# mailboxNotifier.net
KiCad netlist of a schematic drawn in EAGLE
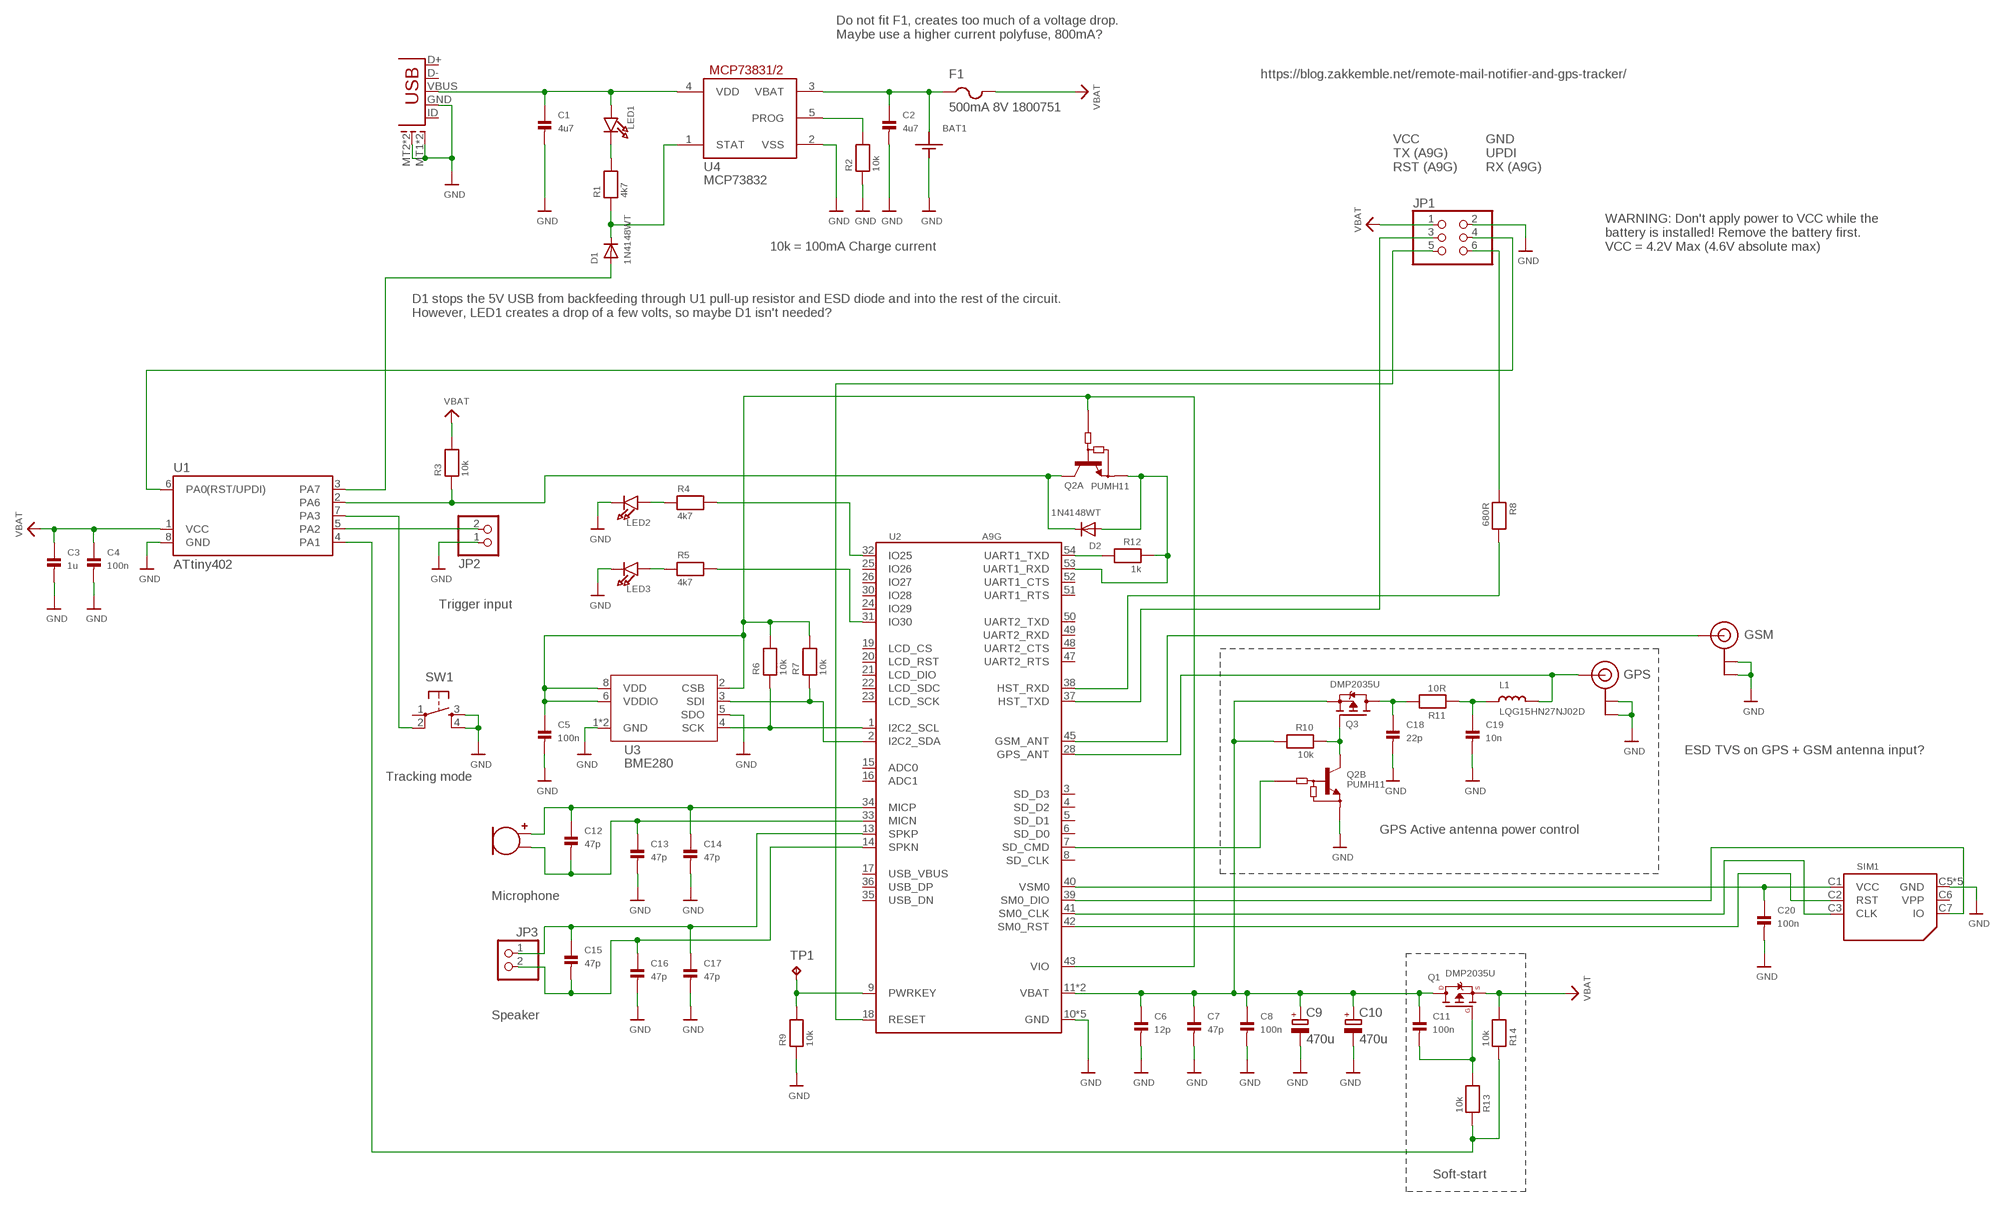
[diagram p0: schematic, sheet 1]

(export (version "E")
  (design (tool "Eeschema 10.0.6"))
  (components
    (comp (ref "BAT1")
      (value "BATTERY_HOLDER1XAAA_PCB")
      (footprint "eagle-import:BATT_HOLDER_AAA_PCB")
      (libsource (lib "eagle-import") (part "BATTERY_HOLDER1XAAA_PCB"))
    )
    (comp (ref "C1")
      (value "4u7")
      (footprint "eagle-import:0805_NO_OUTLINE")
      (libsource (lib "eagle-import") (part "zak_CAP_CERAMIC0805"))
    )
    (comp (ref "C2")
      (value "4u7")
      (footprint "eagle-import:0805_NO_OUTLINE")
      (libsource (lib "eagle-import") (part "zak_CAP_CERAMIC0805"))
    )
    (comp (ref "C3")
      (value "1u")
      (footprint "eagle-import:_0603MP")
      (libsource (lib "eagle-import") (part "CAP_CERAMIC_0603MP"))
    )
    (comp (ref "C4")
      (value "100n")
      (footprint "eagle-import:0402_SMALL")
      (libsource (lib "eagle-import") (part "CAP_CERAMIC0402_SMALL"))
    )
    (comp (ref "C5")
      (value "100n")
      (footprint "eagle-import:0402_SMALL")
      (libsource (lib "eagle-import") (part "CAP_CERAMIC0402_SMALL"))
    )
    (comp (ref "C6")
      (value "12p")
      (footprint "eagle-import:0402_SMALL")
      (libsource (lib "eagle-import") (part "CAP_CERAMIC0402_SMALL"))
    )
    (comp (ref "C7")
      (value "47p")
      (footprint "eagle-import:0402_SMALL")
      (libsource (lib "eagle-import") (part "CAP_CERAMIC0402_SMALL"))
    )
    (comp (ref "C8")
      (value "100n")
      (footprint "eagle-import:0402_SMALL")
      (libsource (lib "eagle-import") (part "CAP_CERAMIC0402_SMALL"))
    )
    (comp (ref "C9")
      (value "470u")
      (footprint "eagle-import:E2,5-6")
      (libsource (lib "eagle-import") (part "CPOL-EUE2.5-6"))
    )
    (comp (ref "C10")
      (value "470u")
      (footprint "eagle-import:E2,5-6")
      (libsource (lib "eagle-import") (part "CPOL-EUE2.5-6"))
    )
    (comp (ref "C11")
      (value "100n")
      (footprint "eagle-import:0402_SMALL")
      (libsource (lib "eagle-import") (part "CAP_CERAMIC0402_SMALL"))
    )
    (comp (ref "C12")
      (value "47p")
      (footprint "eagle-import:0402_SMALL")
      (libsource (lib "eagle-import") (part "CAP_CERAMIC0402_SMALL"))
    )
    (comp (ref "C13")
      (value "47p")
      (footprint "eagle-import:0402_SMALL")
      (libsource (lib "eagle-import") (part "CAP_CERAMIC0402_SMALL"))
    )
    (comp (ref "C14")
      (value "47p")
      (footprint "eagle-import:0402_SMALL")
      (libsource (lib "eagle-import") (part "CAP_CERAMIC0402_SMALL"))
    )
    (comp (ref "C15")
      (value "47p")
      (footprint "eagle-import:0402_SMALL")
      (libsource (lib "eagle-import") (part "CAP_CERAMIC0402_SMALL"))
    )
    (comp (ref "C16")
      (value "47p")
      (footprint "eagle-import:0402_SMALL")
      (libsource (lib "eagle-import") (part "CAP_CERAMIC0402_SMALL"))
    )
    (comp (ref "C17")
      (value "47p")
      (footprint "eagle-import:0402_SMALL")
      (libsource (lib "eagle-import") (part "CAP_CERAMIC0402_SMALL"))
    )
    (comp (ref "C18")
      (value "22p")
      (footprint "eagle-import:0402_SMALL")
      (libsource (lib "eagle-import") (part "CAP_CERAMIC0402_SMALL"))
    )
    (comp (ref "C19")
      (value "10n")
      (footprint "eagle-import:0402_SMALL")
      (libsource (lib "eagle-import") (part "CAP_CERAMIC0402_SMALL"))
    )
    (comp (ref "C20")
      (value "100n")
      (footprint "eagle-import:0402_SMALL")
      (libsource (lib "eagle-import") (part "CAP_CERAMIC0402_SMALL"))
    )
    (comp (ref "D1")
      (value "1N4148WT")
      (footprint "eagle-import:SOD-523")
      (libsource (lib "eagle-import") (part "DIODESOD-523"))
    )
    (comp (ref "D2")
      (value "1N4148WT")
      (footprint "eagle-import:SOD-523")
      (libsource (lib "eagle-import") (part "DIODESOD-523"))
    )
    (comp (ref "F1")
      (value "500mA 8V 1800751")
      (footprint "eagle-import:1206")
      (libsource (lib "eagle-import") (part "PTCFUSE1206"))
    )
    (comp (ref "JP1")
      (value "PINHD-2X3")
      (footprint "eagle-import:2X03")
      (libsource (lib "eagle-import") (part "PINHD-2X3"))
    )
    (comp (ref "JP2")
      (value "PINHD-1X2/90")
      (footprint "eagle-import:1X02_90")
      (libsource (lib "eagle-import") (part "PINHD-1X2/90"))
    )
    (comp (ref "JP3")
      (value "PINHD-1X2")
      (footprint "eagle-import:1X02")
      (libsource (lib "eagle-import") (part "PINHD-1X2"))
    )
    (comp (ref "L1")
      (value "LQG15HN27NJ02D")
      (footprint "eagle-import:0402_SMALL")
      (libsource (lib "eagle-import") (part "INDUCTOR0402_SMALL"))
    )
    (comp (ref "LED1")
      (value "LED0603_NOOUTLINE")
      (footprint "eagle-import:CHIPLED_0603_NOOUTLINE")
      (libsource (lib "eagle-import") (part "LED0603_NOOUTLINE"))
    )
    (comp (ref "LED2")
      (value "LED0603_NOOUTLINE")
      (footprint "eagle-import:CHIPLED_0603_NOOUTLINE")
      (libsource (lib "eagle-import") (part "LED0603_NOOUTLINE"))
    )
    (comp (ref "LED3")
      (value "LED0603_NOOUTLINE")
      (footprint "eagle-import:CHIPLED_0603_NOOUTLINE")
      (libsource (lib "eagle-import") (part "LED0603_NOOUTLINE"))
    )
    (comp (ref "MIC1")
      (value "MIC6MM_RA_SWAP")
      (footprint "eagle-import:MIC6MM_RA_SWAP")
      (libsource (lib "eagle-import") (part "MIC6MM_RA_SWAP"))
    )
    (comp (ref "Q1")
      (value "DMP2035U")
      (footprint "eagle-import:SOT-23-WIDE")
      (libsource (lib "eagle-import") (part "MOSFET-PSOT-23-WIDE"))
    )
    (comp (ref "Q2")
      (value "PUMH11")
      (footprint "eagle-import:SOT-363")
      (libsource (lib "eagle-import") (part "DUAL_NPNDIGITALSOT-363"))
    )
    (comp (ref "Q3")
      (value "DMP2035U")
      (footprint "eagle-import:SOT23-R")
      (libsource (lib "eagle-import") (part "MOSFET-P"))
    )
    (comp (ref "R1")
      (value "4k7")
      (footprint "eagle-import:0402_SMALL")
      (libsource (lib "eagle-import") (part "RESISTOR0402_SMALL"))
    )
    (comp (ref "R2")
      (value "10k")
      (footprint "eagle-import:0402_SMALL")
      (libsource (lib "eagle-import") (part "RESISTOR0402_SMALL"))
    )
    (comp (ref "R3")
      (value "10k")
      (footprint "eagle-import:0402_SMALL")
      (libsource (lib "eagle-import") (part "RESISTOR0402_SMALL"))
    )
    (comp (ref "R4")
      (value "4k7")
      (footprint "eagle-import:0402_SMALL")
      (libsource (lib "eagle-import") (part "RESISTOR0402_SMALL"))
    )
    (comp (ref "R5")
      (value "4k7")
      (footprint "eagle-import:0402_SMALL")
      (libsource (lib "eagle-import") (part "RESISTOR0402_SMALL"))
    )
    (comp (ref "R6")
      (value "10k")
      (footprint "eagle-import:0402_SMALL")
      (libsource (lib "eagle-import") (part "RESISTOR0402_SMALL"))
    )
    (comp (ref "R7")
      (value "10k")
      (footprint "eagle-import:0402_SMALL")
      (libsource (lib "eagle-import") (part "RESISTOR0402_SMALL"))
    )
    (comp (ref "R8")
      (value "680R")
      (footprint "eagle-import:0402_SMALL")
      (libsource (lib "eagle-import") (part "RESISTOR0402_SMALL"))
    )
    (comp (ref "R9")
      (value "10k")
      (footprint "eagle-import:0402_SMALL")
      (libsource (lib "eagle-import") (part "RESISTOR0402_SMALL"))
    )
    (comp (ref "R10")
      (value "10k")
      (footprint "eagle-import:0402_SMALL")
      (libsource (lib "eagle-import") (part "RESISTOR0402_SMALL"))
    )
    (comp (ref "R11")
      (value "10R")
      (footprint "eagle-import:0402_SMALL")
      (libsource (lib "eagle-import") (part "RESISTOR0402_SMALL"))
    )
    (comp (ref "R12")
      (value "1k")
      (footprint "eagle-import:0402_SMALL")
      (libsource (lib "eagle-import") (part "RESISTOR0402_SMALL"))
    )
    (comp (ref "R13")
      (value "10k")
      (footprint "eagle-import:0402_SMALL")
      (libsource (lib "eagle-import") (part "RESISTOR0402_SMALL"))
    )
    (comp (ref "R14")
      (value "10k")
      (footprint "eagle-import:0402_SMALL")
      (libsource (lib "eagle-import") (part "RESISTOR0402_SMALL"))
    )
    (comp (ref "SIM1")
      (value "SIMCARDSOCKET")
      (footprint "eagle-import:SIM_SOCKET1")
      (libsource (lib "eagle-import") (part "SIMCARDSOCKET"))
    )
    (comp (ref "SW1")
      (value "SPST_TACTG75_3X4")
      (footprint "eagle-import:TACT_SMD5")
      (libsource (lib "eagle-import") (part "SPST_TACTG75_3X4"))
    )
    (comp (ref "TP1")
      (value "TPTP10R")
      (footprint "eagle-import:TP10R")
      (libsource (lib "eagle-import") (part "TPTP10R"))
    )
    (comp (ref "U$38")
      (value "U.FL")
      (footprint "eagle-import:U.FL")
      (libsource (lib "eagle-import") (part "U.FL"))
    )
    (comp (ref "U$55")
      (value "U.FL")
      (footprint "eagle-import:U.FL")
      (libsource (lib "eagle-import") (part "U.FL"))
    )
    (comp (ref "U1")
      (value "ATtiny402")
      (footprint "eagle-import:SOIC8_150MIL_SMPAD")
      (libsource (lib "eagle-import") (part "ATTINY402SOIC8"))
    )
    (comp (ref "U2")
      (value "A9G")
      (footprint "eagle-import:A9G")
      (libsource (lib "eagle-import") (part "A9G"))
    )
    (comp (ref "U3")
      (value "BME280")
      (footprint "eagle-import:BME280")
      (libsource (lib "eagle-import") (part "BME280"))
    )
    (comp (ref "U4")
      (value "MCP73831/OT")
      (footprint "eagle-import:SOT23-5L")
      (libsource (lib "eagle-import") (part "MCP73831/OT"))
    )
    (comp (ref "USB1")
      (value "USB-MICROBSAFEBEE")
      (footprint "eagle-import:USB-MICROB_SAFEBEE")
      (libsource (lib "eagle-import") (part "USB-MICROBSAFEBEE"))
    )
  )
  (nets
    (net (code "1") (name "GND") (class "Default")
      (node (ref "BAT1") (pin "NEG") (pinfunction "NEG_NEG") (pintype "passive"))
      (node (ref "C1") (pin "2") (pinfunction "P$2_2") (pintype "passive"))
      (node (ref "C10") (pin "-") (pinfunction "-_-") (pintype "passive"))
      (node (ref "C13") (pin "2") (pinfunction "P$2_2") (pintype "passive"))
      (node (ref "C14") (pin "2") (pinfunction "P$2_2") (pintype "passive"))
      (node (ref "C16") (pin "2") (pinfunction "P$2_2") (pintype "passive"))
      (node (ref "C17") (pin "2") (pinfunction "P$2_2") (pintype "passive"))
      (node (ref "C18") (pin "2") (pinfunction "P$2_2") (pintype "passive"))
      (node (ref "C19") (pin "2") (pinfunction "P$2_2") (pintype "passive"))
      (node (ref "C2") (pin "2") (pinfunction "P$2_2") (pintype "passive"))
      (node (ref "C20") (pin "2") (pinfunction "P$2_2") (pintype "passive"))
      (node (ref "C3") (pin "2") (pinfunction "P$2_2") (pintype "passive"))
      (node (ref "C4") (pin "2") (pinfunction "P$2_2") (pintype "passive"))
      (node (ref "C5") (pin "2") (pinfunction "P$2_2") (pintype "passive"))
      (node (ref "C6") (pin "2") (pinfunction "P$2_2") (pintype "passive"))
      (node (ref "C7") (pin "2") (pinfunction "P$2_2") (pintype "passive"))
      (node (ref "C8") (pin "2") (pinfunction "P$2_2") (pintype "passive"))
      (node (ref "C9") (pin "-") (pinfunction "-_-") (pintype "passive"))
      (node (ref "JP1") (pin "2") (pinfunction "2_2") (pintype "passive"))
      (node (ref "JP2") (pin "1") (pinfunction "1_1") (pintype "passive"))
      (node (ref "LED2") (pin "C") (pinfunction "C_C") (pintype "passive"))
      (node (ref "LED3") (pin "C") (pinfunction "C_C") (pintype "passive"))
      (node (ref "Q2") (pin "4") (pinfunction "E_4") (pintype "passive"))
      (node (ref "R2") (pin "1") (pinfunction "1_1") (pintype "passive"))
      (node (ref "R9") (pin "1") (pinfunction "1_1") (pintype "passive"))
      (node (ref "SIM1") (pin "C5") (pinfunction "GND_C5") (pintype "bidirectional"))
      (node (ref "SIM1") (pin "GND1") (pinfunction "GND_GND1") (pintype "bidirectional"))
      (node (ref "SIM1") (pin "GND2") (pinfunction "GND_GND2") (pintype "bidirectional"))
      (node (ref "SIM1") (pin "GND3") (pinfunction "GND_GND3") (pintype "bidirectional"))
      (node (ref "SIM1") (pin "GND4") (pinfunction "GND_GND4") (pintype "bidirectional"))
      (node (ref "SW1") (pin "3") (pinfunction "S_3") (pintype "passive"))
      (node (ref "SW1") (pin "4") (pinfunction "S1_4") (pintype "passive"))
      (node (ref "U$38") (pin "1") (pinfunction "GND_1") (pintype "passive"))
      (node (ref "U$38") (pin "2") (pinfunction "GND_2") (pintype "passive"))
      (node (ref "U$55") (pin "1") (pinfunction "GND_1") (pintype "passive"))
      (node (ref "U$55") (pin "2") (pinfunction "GND_2") (pintype "passive"))
      (node (ref "U1") (pin "8") (pinfunction "GND_8") (pintype "power_in"))
      (node (ref "U2") (pin "10") (pinfunction "GND_10") (pintype "bidirectional"))
      (node (ref "U2") (pin "27") (pinfunction "GND_27") (pintype "bidirectional"))
      (node (ref "U2") (pin "29") (pinfunction "GND_29") (pintype "bidirectional"))
      (node (ref "U2") (pin "44") (pinfunction "GND_44") (pintype "bidirectional"))
      (node (ref "U2") (pin "46") (pinfunction "GND_46") (pintype "bidirectional"))
      (node (ref "U3") (pin "1") (pinfunction "GND_1") (pintype "bidirectional"))
      (node (ref "U3") (pin "5") (pinfunction "SDO_5") (pintype "bidirectional"))
      (node (ref "U3") (pin "7") (pinfunction "GND_7") (pintype "bidirectional"))
      (node (ref "U4") (pin "2") (pinfunction "VSS_2") (pintype "power_in"))
      (node (ref "USB1") (pin "GND") (pinfunction "GND_GND") (pintype "bidirectional"))
      (node (ref "USB1") (pin "MT1") (pinfunction "SHEILD1_MT1") (pintype "bidirectional"))
      (node (ref "USB1") (pin "MT2") (pinfunction "SHEILD2_MT2") (pintype "bidirectional"))
      (node (ref "USB1") (pin "MT3") (pinfunction "SHEILD1_MT3") (pintype "bidirectional"))
      (node (ref "USB1") (pin "MT4") (pinfunction "SHEILD2_MT4") (pintype "bidirectional"))
    )
    (net (code "2") (name "Net-(C1-P$1)") (class "Default")
      (node (ref "C1") (pin "1") (pinfunction "P$1_1") (pintype "passive"))
      (node (ref "LED1") (pin "A") (pinfunction "A_A") (pintype "passive"))
      (node (ref "U4") (pin "4") (pinfunction "VDD_4") (pintype "power_in"))
      (node (ref "USB1") (pin "VBUS") (pinfunction "VBUS_VBUS") (pintype "bidirectional"))
    )
    (net (code "3") (name "Net-(C2-P$1)") (class "Default")
      (node (ref "BAT1") (pin "POS") (pinfunction "POS_POS") (pintype "power_in"))
      (node (ref "C2") (pin "1") (pinfunction "P$1_1") (pintype "passive"))
      (node (ref "F1") (pin "1") (pinfunction "1_1") (pintype "passive"))
      (node (ref "U4") (pin "3") (pinfunction "VBAT_3") (pintype "bidirectional"))
    )
    (net (code "4") (name "Net-(C5-P$1)") (class "Default")
      (node (ref "C5") (pin "1") (pinfunction "P$1_1") (pintype "passive"))
      (node (ref "Q2") (pin "2") (pinfunction "B_2") (pintype "passive"))
      (node (ref "R6") (pin "2") (pinfunction "2_2") (pintype "passive"))
      (node (ref "R7") (pin "2") (pinfunction "2_2") (pintype "passive"))
      (node (ref "U2") (pin "43") (pinfunction "VIO_43") (pintype "bidirectional"))
      (node (ref "U3") (pin "2") (pinfunction "CSB_2") (pintype "bidirectional"))
      (node (ref "U3") (pin "6") (pinfunction "VDDIO_6") (pintype "bidirectional"))
      (node (ref "U3") (pin "8") (pinfunction "VDD_8") (pintype "bidirectional"))
    )
    (net (code "5") (name "Net-(C11-P$1)") (class "Default")
      (node (ref "C10") (pin "+") (pinfunction "+_+") (pintype "passive"))
      (node (ref "C11") (pin "1") (pinfunction "P$1_1") (pintype "passive"))
      (node (ref "C6") (pin "1") (pinfunction "P$1_1") (pintype "passive"))
      (node (ref "C7") (pin "1") (pinfunction "P$1_1") (pintype "passive"))
      (node (ref "C8") (pin "1") (pinfunction "P$1_1") (pintype "passive"))
      (node (ref "C9") (pin "+") (pinfunction "+_+") (pintype "passive"))
      (node (ref "Q1") (pin "3") (pinfunction "D_3") (pintype "passive"))
      (node (ref "Q3") (pin "2") (pinfunction "S_2") (pintype "passive"))
      (node (ref "R10") (pin "2") (pinfunction "2_2") (pintype "passive"))
      (node (ref "U2") (pin "11") (pinfunction "VBAT_11") (pintype "bidirectional"))
      (node (ref "U2") (pin "12") (pinfunction "VBAT_12") (pintype "bidirectional"))
    )
    (net (code "6") (name "Net-(C11-P$2)") (class "Default")
      (node (ref "C11") (pin "2") (pinfunction "P$2_2") (pintype "passive"))
      (node (ref "Q1") (pin "1") (pinfunction "G_1") (pintype "passive"))
      (node (ref "R13") (pin "2") (pinfunction "2_2") (pintype "passive"))
    )
    (net (code "7") (name "Net-(C12-P$1)") (class "Default")
      (node (ref "C12") (pin "1") (pinfunction "P$1_1") (pintype "passive"))
      (node (ref "C14") (pin "1") (pinfunction "P$1_1") (pintype "passive"))
      (node (ref "MIC1") (pin "POS") (pinfunction "POS_POS") (pintype "bidirectional"))
      (node (ref "U2") (pin "34") (pinfunction "MICP_34") (pintype "bidirectional"))
    )
    (net (code "8") (name "Net-(C12-P$2)") (class "Default")
      (node (ref "C12") (pin "2") (pinfunction "P$2_2") (pintype "passive"))
      (node (ref "C13") (pin "1") (pinfunction "P$1_1") (pintype "passive"))
      (node (ref "MIC1") (pin "NEG") (pinfunction "NEG_NEG") (pintype "bidirectional"))
      (node (ref "U2") (pin "33") (pinfunction "MICN_33") (pintype "bidirectional"))
    )
    (net (code "9") (name "Net-(C15-P$1)") (class "Default")
      (node (ref "C15") (pin "1") (pinfunction "P$1_1") (pintype "passive"))
      (node (ref "C17") (pin "1") (pinfunction "P$1_1") (pintype "passive"))
      (node (ref "JP3") (pin "1") (pinfunction "1_1") (pintype "passive"))
      (node (ref "U2") (pin "13") (pinfunction "SPKP_13") (pintype "bidirectional"))
    )
    (net (code "10") (name "Net-(C15-P$2)") (class "Default")
      (node (ref "C15") (pin "2") (pinfunction "P$2_2") (pintype "passive"))
      (node (ref "C16") (pin "1") (pinfunction "P$1_1") (pintype "passive"))
      (node (ref "JP3") (pin "2") (pinfunction "2_2") (pintype "passive"))
      (node (ref "U2") (pin "14") (pinfunction "SPKN_14") (pintype "bidirectional"))
    )
    (net (code "11") (name "Net-(C18-P$1)") (class "Default")
      (node (ref "C18") (pin "1") (pinfunction "P$1_1") (pintype "passive"))
      (node (ref "Q3") (pin "3") (pinfunction "D_3") (pintype "passive"))
      (node (ref "R11") (pin "2") (pinfunction "2_2") (pintype "passive"))
    )
    (net (code "12") (name "Net-(C19-P$1)") (class "Default")
      (node (ref "C19") (pin "1") (pinfunction "P$1_1") (pintype "passive"))
      (node (ref "L1") (pin "1") (pinfunction "1_1") (pintype "passive"))
      (node (ref "R11") (pin "1") (pinfunction "1_1") (pintype "passive"))
    )
    (net (code "13") (name "Net-(C20-P$1)") (class "Default")
      (node (ref "C20") (pin "1") (pinfunction "P$1_1") (pintype "passive"))
      (node (ref "SIM1") (pin "C1") (pinfunction "VCC_C1") (pintype "bidirectional"))
      (node (ref "U2") (pin "40") (pinfunction "VSM0_40") (pintype "bidirectional"))
    )
    (net (code "14") (name "Net-(D1-C)") (class "Default")
      (node (ref "D1") (pin "K") (pinfunction "C_K") (pintype "passive"))
      (node (ref "R1") (pin "1") (pinfunction "1_1") (pintype "passive"))
      (node (ref "U4") (pin "1") (pinfunction "STAT_1") (pintype "output"))
    )
    (net (code "15") (name "Net-(D2-C)") (class "Default")
      (node (ref "D2") (pin "K") (pinfunction "C_K") (pintype "passive"))
      (node (ref "Q2") (pin "6") (pinfunction "C_6") (pintype "passive"))
      (node (ref "R3") (pin "1") (pinfunction "1_1") (pintype "passive"))
      (node (ref "U1") (pin "2") (pinfunction "PA6_2") (pintype "bidirectional"))
    )
    (net (code "16") (name "Net-(JP1-Pad6)") (class "Default")
      (node (ref "JP1") (pin "6") (pinfunction "6_6") (pintype "passive"))
      (node (ref "R8") (pin "1") (pinfunction "1_1") (pintype "passive"))
    )
    (net (code "17") (name "Net-(LED1-PadC)") (class "Default")
      (node (ref "LED1") (pin "C") (pinfunction "C_C") (pintype "passive"))
      (node (ref "R1") (pin "2") (pinfunction "2_2") (pintype "passive"))
    )
    (net (code "18") (name "Net-(LED2-PadA)") (class "Default")
      (node (ref "LED2") (pin "A") (pinfunction "A_A") (pintype "passive"))
      (node (ref "R4") (pin "1") (pinfunction "1_1") (pintype "passive"))
    )
    (net (code "19") (name "Net-(LED3-PadA)") (class "Default")
      (node (ref "LED3") (pin "A") (pinfunction "A_A") (pintype "passive"))
      (node (ref "R5") (pin "1") (pinfunction "1_1") (pintype "passive"))
    )
    (net (code "20") (name "Net-(Q2A-E)") (class "Default")
      (node (ref "D2") (pin "A") (pinfunction "A_A") (pintype "passive"))
      (node (ref "Q2") (pin "1") (pinfunction "E_1") (pintype "passive"))
      (node (ref "R12") (pin "1") (pinfunction "1_1") (pintype "passive"))
      (node (ref "U2") (pin "53") (pinfunction "UART1_RXD_53") (pintype "bidirectional"))
    )
    (net (code "21") (name "Net-(Q2B-B)") (class "Default")
      (node (ref "Q2") (pin "5") (pinfunction "B_5") (pintype "passive"))
      (node (ref "U2") (pin "7") (pinfunction "SD_CMD_7") (pintype "bidirectional"))
    )
    (net (code "22") (name "Net-(Q2B-C)") (class "Default")
      (node (ref "Q2") (pin "3") (pinfunction "C_3") (pintype "passive"))
      (node (ref "Q3") (pin "1") (pinfunction "G_1") (pintype "passive"))
      (node (ref "R10") (pin "1") (pinfunction "1_1") (pintype "passive"))
    )
    (net (code "23") (name "Net-(SIM1-CLK)") (class "Default")
      (node (ref "SIM1") (pin "C3") (pinfunction "CLK_C3") (pintype "bidirectional"))
      (node (ref "U2") (pin "41") (pinfunction "SM0_CLK_41") (pintype "bidirectional"))
    )
    (net (code "24") (name "Net-(SIM1-IO)") (class "Default")
      (node (ref "SIM1") (pin "C7") (pinfunction "IO_C7") (pintype "bidirectional"))
      (node (ref "U2") (pin "39") (pinfunction "SM0_DIO_39") (pintype "bidirectional"))
    )
    (net (code "25") (name "Net-(SIM1-RST)") (class "Default")
      (node (ref "SIM1") (pin "C2") (pinfunction "RST_C2") (pintype "bidirectional"))
      (node (ref "U2") (pin "42") (pinfunction "SM0_RST_42") (pintype "bidirectional"))
    )
    (net (code "26") (name "Net-(SW1-P1)") (class "Default")
      (node (ref "SW1") (pin "2") (pinfunction "P1_2") (pintype "passive"))
      (node (ref "U1") (pin "7") (pinfunction "PA3_7") (pintype "bidirectional"))
    )
    (net (code "27") (name "Net-(U$38-SIGNAL)") (class "Default")
      (node (ref "L1") (pin "2") (pinfunction "2_2") (pintype "passive"))
      (node (ref "U$38") (pin "3") (pinfunction "SIGNAL_3") (pintype "passive"))
      (node (ref "U2") (pin "28") (pinfunction "GPS_ANT_28") (pintype "bidirectional"))
    )
    (net (code "28") (name "Net-(U$55-SIGNAL)") (class "Default")
      (node (ref "U$55") (pin "3") (pinfunction "SIGNAL_3") (pintype "passive"))
      (node (ref "U2") (pin "45") (pinfunction "GSM_ANT_45") (pintype "bidirectional"))
    )
    (net (code "29") (name "Net-(U1-PA0(RST{slash}UPDI))") (class "Default")
      (node (ref "JP1") (pin "4") (pinfunction "4_4") (pintype "passive"))
      (node (ref "U1") (pin "6") (pinfunction "PA0(RST/UPDI)_6") (pintype "input"))
    )
    (net (code "30") (name "Net-(U1-PA1)") (class "Default")
      (node (ref "R13") (pin "1") (pinfunction "1_1") (pintype "passive"))
      (node (ref "R14") (pin "1") (pinfunction "1_1") (pintype "passive"))
      (node (ref "U1") (pin "4") (pinfunction "PA1_4") (pintype "bidirectional"))
    )
    (net (code "31") (name "Net-(U1-PA2)") (class "Default")
      (node (ref "JP2") (pin "2") (pinfunction "2_2") (pintype "passive"))
      (node (ref "U1") (pin "5") (pinfunction "PA2_5") (pintype "bidirectional"))
    )
    (net (code "32") (name "Net-(U1-PA7)") (class "Default")
      (node (ref "D1") (pin "A") (pinfunction "A_A") (pintype "passive"))
      (node (ref "U1") (pin "3") (pinfunction "PA7_3") (pintype "bidirectional"))
    )
    (net (code "33") (name "Net-(U2-HST_RXD)") (class "Default")
      (node (ref "R8") (pin "2") (pinfunction "2_2") (pintype "passive"))
      (node (ref "U2") (pin "38") (pinfunction "HST_RXD_38") (pintype "bidirectional"))
    )
    (net (code "34") (name "Net-(U2-HST_TXD)") (class "Default")
      (node (ref "JP1") (pin "3") (pinfunction "3_3") (pintype "passive"))
      (node (ref "U2") (pin "37") (pinfunction "HST_TXD_37") (pintype "bidirectional"))
    )
    (net (code "35") (name "Net-(U2-I2C2_SCL)") (class "Default")
      (node (ref "R6") (pin "1") (pinfunction "1_1") (pintype "passive"))
      (node (ref "U2") (pin "1") (pinfunction "I2C2_SCL_1") (pintype "bidirectional"))
      (node (ref "U3") (pin "4") (pinfunction "SCK_4") (pintype "bidirectional"))
    )
    (net (code "36") (name "Net-(U2-I2C2_SDA)") (class "Default")
      (node (ref "R7") (pin "1") (pinfunction "1_1") (pintype "passive"))
      (node (ref "U2") (pin "2") (pinfunction "I2C2_SDA_2") (pintype "bidirectional"))
      (node (ref "U3") (pin "3") (pinfunction "SDI_3") (pintype "bidirectional"))
    )
    (net (code "37") (name "Net-(U2-IO25)") (class "Default")
      (node (ref "R4") (pin "2") (pinfunction "2_2") (pintype "passive"))
      (node (ref "U2") (pin "32") (pinfunction "IO25_32") (pintype "bidirectional"))
    )
    (net (code "38") (name "Net-(U2-IO30)") (class "Default")
      (node (ref "R5") (pin "2") (pinfunction "2_2") (pintype "passive"))
      (node (ref "U2") (pin "31") (pinfunction "IO30_31") (pintype "bidirectional"))
    )
    (net (code "39") (name "Net-(U2-PWRKEY)") (class "Default")
      (node (ref "R9") (pin "2") (pinfunction "2_2") (pintype "passive"))
      (node (ref "TP1") (pin "TP") (pinfunction "TP_TP") (pintype "input"))
      (node (ref "U2") (pin "9") (pinfunction "PWRKEY_9") (pintype "bidirectional"))
    )
    (net (code "40") (name "Net-(U2-RESET)") (class "Default")
      (node (ref "JP1") (pin "5") (pinfunction "5_5") (pintype "passive"))
      (node (ref "U2") (pin "18") (pinfunction "RESET_18") (pintype "bidirectional"))
    )
    (net (code "41") (name "Net-(U2-UART1_TXD)") (class "Default")
      (node (ref "R12") (pin "2") (pinfunction "2_2") (pintype "passive"))
      (node (ref "U2") (pin "54") (pinfunction "UART1_TXD_54") (pintype "bidirectional"))
    )
    (net (code "42") (name "Net-(U4-PROG)") (class "Default")
      (node (ref "R2") (pin "2") (pinfunction "2_2") (pintype "passive"))
      (node (ref "U4") (pin "5") (pinfunction "PROG_5") (pintype "input"))
    )
    (net (code "43") (name "VBAT") (class "Default")
      (node (ref "C3") (pin "1") (pinfunction "P$1_1") (pintype "passive"))
      (node (ref "C4") (pin "1") (pinfunction "P$1_1") (pintype "passive"))
      (node (ref "F1") (pin "2") (pinfunction "2_2") (pintype "passive"))
      (node (ref "JP1") (pin "1") (pinfunction "1_1") (pintype "passive"))
      (node (ref "Q1") (pin "2") (pinfunction "S_2") (pintype "passive"))
      (node (ref "R14") (pin "2") (pinfunction "2_2") (pintype "passive"))
      (node (ref "R3") (pin "2") (pinfunction "2_2") (pintype "passive"))
      (node (ref "U1") (pin "1") (pinfunction "VCC_1") (pintype "power_in"))
    )
    (net (code "44") (name "unconnected-(SIM1-VPP-PadC6)") (class "Default")
      (node (ref "SIM1") (pin "C6") (pinfunction "VPP_C6") (pintype "bidirectional"))
    )
    (net (code "45") (name "unconnected-(SW1-P-Pad1)") (class "Default")
      (node (ref "SW1") (pin "1") (pinfunction "P_1") (pintype "passive"))
    )
    (net (code "46") (name "unconnected-(U2-ADC0-Pad15)") (class "Default")
      (node (ref "U2") (pin "15") (pinfunction "ADC0_15") (pintype "bidirectional"))
    )
    (net (code "47") (name "unconnected-(U2-ADC1-Pad16)") (class "Default")
      (node (ref "U2") (pin "16") (pinfunction "ADC1_16") (pintype "bidirectional"))
    )
    (net (code "48") (name "unconnected-(U2-IO26-Pad25)") (class "Default")
      (node (ref "U2") (pin "25") (pinfunction "IO26_25") (pintype "bidirectional"))
    )
    (net (code "49") (name "unconnected-(U2-IO27-Pad26)") (class "Default")
      (node (ref "U2") (pin "26") (pinfunction "IO27_26") (pintype "bidirectional"))
    )
    (net (code "50") (name "unconnected-(U2-IO28-Pad30)") (class "Default")
      (node (ref "U2") (pin "30") (pinfunction "IO28_30") (pintype "bidirectional"))
    )
    (net (code "51") (name "unconnected-(U2-IO29-Pad24)") (class "Default")
      (node (ref "U2") (pin "24") (pinfunction "IO29_24") (pintype "bidirectional"))
    )
    (net (code "52") (name "unconnected-(U2-LCD_CS-Pad19)") (class "Default")
      (node (ref "U2") (pin "19") (pinfunction "LCD_CS_19") (pintype "bidirectional"))
    )
    (net (code "53") (name "unconnected-(U2-LCD_DIO-Pad21)") (class "Default")
      (node (ref "U2") (pin "21") (pinfunction "LCD_DIO_21") (pintype "bidirectional"))
    )
    (net (code "54") (name "unconnected-(U2-LCD_RST-Pad20)") (class "Default")
      (node (ref "U2") (pin "20") (pinfunction "LCD_RST_20") (pintype "bidirectional"))
    )
    (net (code "55") (name "unconnected-(U2-LCD_SCK-Pad23)") (class "Default")
      (node (ref "U2") (pin "23") (pinfunction "LCD_SCK_23") (pintype "bidirectional"))
    )
    (net (code "56") (name "unconnected-(U2-LCD_SDC-Pad22)") (class "Default")
      (node (ref "U2") (pin "22") (pinfunction "LCD_SDC_22") (pintype "bidirectional"))
    )
    (net (code "57") (name "unconnected-(U2-SD_CLK-Pad8)") (class "Default")
      (node (ref "U2") (pin "8") (pinfunction "SD_CLK_8") (pintype "bidirectional"))
    )
    (net (code "58") (name "unconnected-(U2-SD_D0-Pad6)") (class "Default")
      (node (ref "U2") (pin "6") (pinfunction "SD_D0_6") (pintype "bidirectional"))
    )
    (net (code "59") (name "unconnected-(U2-SD_D1-Pad5)") (class "Default")
      (node (ref "U2") (pin "5") (pinfunction "SD_D1_5") (pintype "bidirectional"))
    )
    (net (code "60") (name "unconnected-(U2-SD_D2-Pad4)") (class "Default")
      (node (ref "U2") (pin "4") (pinfunction "SD_D2_4") (pintype "bidirectional"))
    )
    (net (code "61") (name "unconnected-(U2-SD_D3-Pad3)") (class "Default")
      (node (ref "U2") (pin "3") (pinfunction "SD_D3_3") (pintype "bidirectional"))
    )
    (net (code "62") (name "unconnected-(U2-UART1_CTS-Pad52)") (class "Default")
      (node (ref "U2") (pin "52") (pinfunction "UART1_CTS_52") (pintype "bidirectional"))
    )
    (net (code "63") (name "unconnected-(U2-UART1_RTS-Pad51)") (class "Default")
      (node (ref "U2") (pin "51") (pinfunction "UART1_RTS_51") (pintype "bidirectional"))
    )
    (net (code "64") (name "unconnected-(U2-UART2_CTS-Pad48)") (class "Default")
      (node (ref "U2") (pin "48") (pinfunction "UART2_CTS_48") (pintype "bidirectional"))
    )
    (net (code "65") (name "unconnected-(U2-UART2_RTS-Pad47)") (class "Default")
      (node (ref "U2") (pin "47") (pinfunction "UART2_RTS_47") (pintype "bidirectional"))
    )
    (net (code "66") (name "unconnected-(U2-UART2_RXD-Pad49)") (class "Default")
      (node (ref "U2") (pin "49") (pinfunction "UART2_RXD_49") (pintype "bidirectional"))
    )
    (net (code "67") (name "unconnected-(U2-UART2_TXD-Pad50)") (class "Default")
      (node (ref "U2") (pin "50") (pinfunction "UART2_TXD_50") (pintype "bidirectional"))
    )
    (net (code "68") (name "unconnected-(U2-USB_DN-Pad35)") (class "Default")
      (node (ref "U2") (pin "35") (pinfunction "USB_DN_35") (pintype "bidirectional"))
    )
    (net (code "69") (name "unconnected-(U2-USB_DP-Pad36)") (class "Default")
      (node (ref "U2") (pin "36") (pinfunction "USB_DP_36") (pintype "bidirectional"))
    )
    (net (code "70") (name "unconnected-(U2-USB_VBUS-Pad17)") (class "Default")
      (node (ref "U2") (pin "17") (pinfunction "USB_VBUS_17") (pintype "bidirectional"))
    )
    (net (code "71") (name "unconnected-(USB1-PadD+)") (class "Default")
      (node (ref "USB1") (pin "D+") (pinfunction "D+_D+") (pintype "bidirectional"))
    )
    (net (code "72") (name "unconnected-(USB1-PadD-)") (class "Default")
      (node (ref "USB1") (pin "D-") (pinfunction "D-_D-") (pintype "bidirectional"))
    )
    (net (code "73") (name "unconnected-(USB1-PadID)") (class "Default")
      (node (ref "USB1") (pin "ID") (pinfunction "ID_ID") (pintype "bidirectional"))
    )
  )
)
